# Communication.net
KiCad netlist of a schematic drawn in Altium Designer
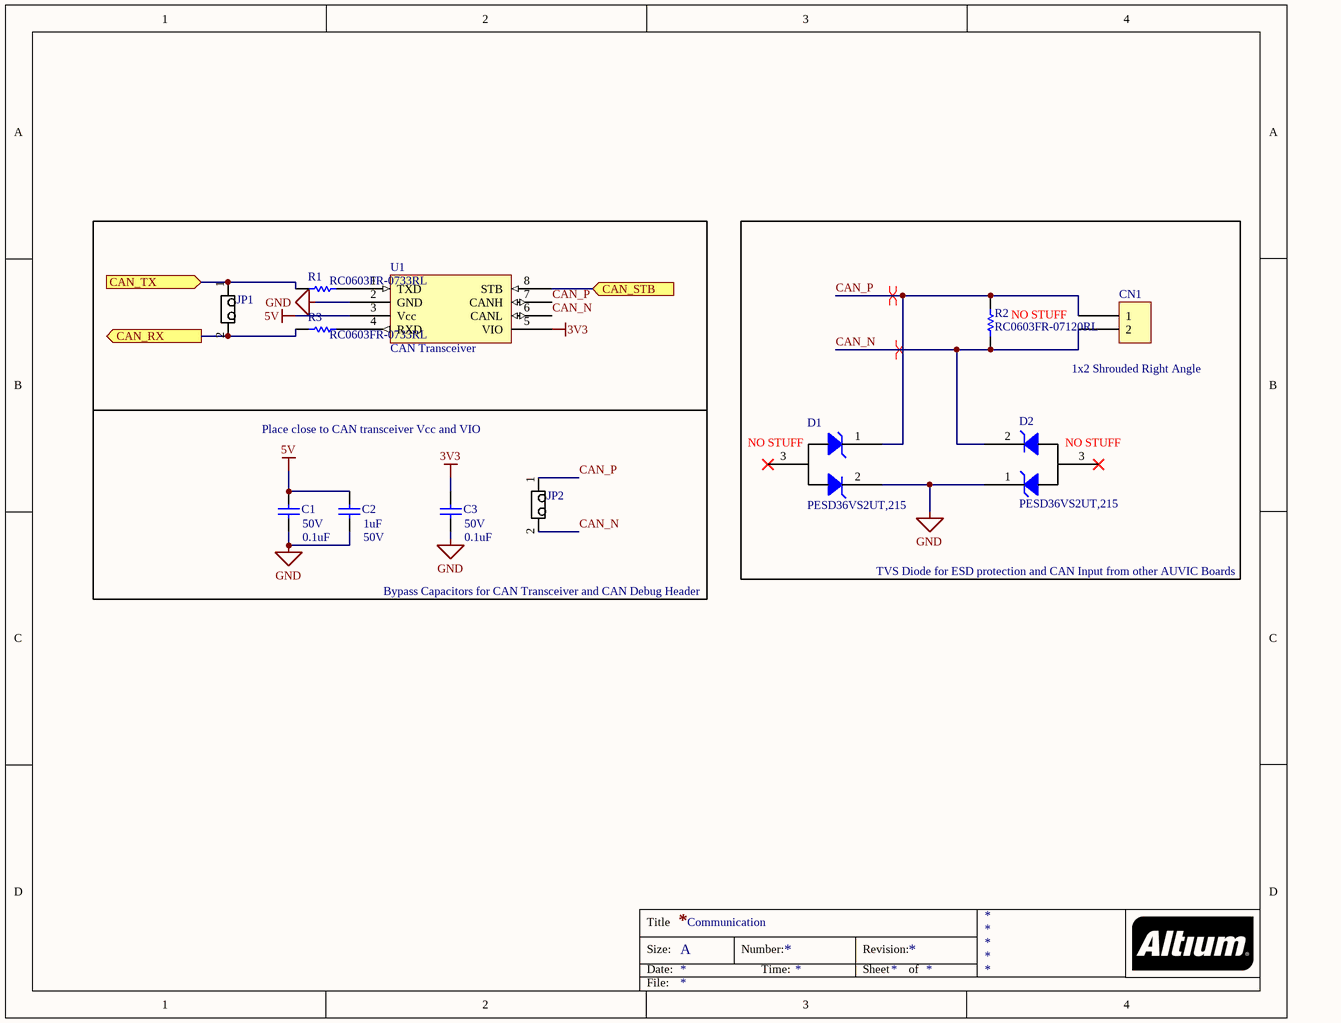
[diagram p0: Communication.SchDoc]

(export (version "E")
  (design (tool "Eeschema 10.0.6"))
  (components
    (comp (ref "C1")
      (value "CL10B104JB8NNNC")
      (footprint "FP-CL10-0_1-IPC_A")
      (description "CAP CER 0.1UF 50V X7R 0603")
      (fields
        (field (name "TOLERANCE") "5%")
        (field (name "VOLTAGE") "50V")
        (field (name "CAPACITANCE") "0.1uF")
      )
      (libsource (lib "AUVIC") (part "CAP-NP-2"))
    )
    (comp (ref "C2")
      (value "CL21B105KBFNNNG")
      (footprint "0803 CAP")
      (description "SAMSUNG ELECTRO-MECHANICS - CL21B105KBFNNNG - MLCC CAPACITORS")
      (fields
        (field (name "TOLERANCE") "10%")
        (field (name "CAPACITANCE") "1uF")
        (field (name "VOLTAGE") "50V")
      )
      (libsource (lib "AUVIC") (part "Symbol"))
    )
    (comp (ref "C3")
      (value "CL10B104JB8NNNC")
      (footprint "FP-CL10-0_1-IPC_A")
      (description "CAP CER 0.1UF 50V X7R 0603")
      (fields
        (field (name "TOLERANCE") "5%")
        (field (name "VOLTAGE") "50V")
        (field (name "CAPACITANCE") "0.1uF")
      )
      (libsource (lib "AUVIC") (part "CAP-NP-2"))
    )
    (comp (ref "CN1")
      (value "1x2 Shrouded Right Angle")
      (footprint "2X1 Female Header")
      (description "02 MTE HDR SRRA LATCH")
      (libsource (lib "AUVIC") (part "1x2 Shrouded Right Angle"))
    )
    (comp (ref "D1")
      (value "PESD36VS2UT,215")
      (footprint "SOT95P245X110-3N")
      (description "TVS DIODE 36V 60V SOT23")
      (fields (field (name "CREATED BY") "Miguel Manguerra"))
      (libsource (lib "AUVIC") (part "PESD36VS2UT,215"))
    )
    (comp (ref "D2")
      (value "PESD36VS2UT,215")
      (footprint "SOT95P245X110-3N")
      (description "TVS DIODE 36V 60V SOT23")
      (fields (field (name "CREATED BY") "Miguel Manguerra"))
      (libsource (lib "AUVIC") (part "PESD36VS2UT,215"))
    )
    (comp (ref "JP1")
      (value "1x2 Male Header")
      (footprint "2X1 Males Header")
      (fields (field (name "MADE BY") "Andy Bates"))
      (libsource (lib "AUVIC") (part "1x2 Male Header"))
    )
    (comp (ref "JP2")
      (value "1x2 Male Header")
      (footprint "2X1 Males Header")
      (fields (field (name "MADE BY") "Andy Bates"))
      (libsource (lib "AUVIC") (part "1x2 Male Header"))
    )
    (comp (ref "R1")
      (value "RC0603FR-0733RL")
      (footprint "RESC1608X55X25LL10T15")
      (description "Res Thick Film 0603 33 Ohm 1% 1/10W +/-100ppm/ßC Molded SMD Paper T/R")
      (fields (field (name "TOLERANCE") "1%"))
      (libsource (lib "AUVIC") (part "RES-2"))
    )
    (comp (ref "R2")
      (value "RC0603FR-07120RL")
      (footprint "RESC1608X55X25ML10T15")
      (description "Res Thick Film 0603 120 Ohm 1% 0.1W(1/10W) ±100ppm/C Epoxy SMD T/R")
      (fields (field (name "TOLERANCE") "1%"))
      (libsource (lib "AUVIC") (part "RES-2"))
    )
    (comp (ref "R3")
      (value "RC0603FR-0733RL")
      (footprint "RESC1608X55X25LL10T15")
      (description "Res Thick Film 0603 33 Ohm 1% 1/10W +/-100ppm/ßC Molded SMD Paper T/R")
      (fields (field (name "TOLERANCE") "1%"))
      (libsource (lib "AUVIC") (part "RES-2"))
    )
    (comp (ref "U1")
      (value "CAN Transceiver")
      (footprint "8-SOIC")
      (description "1/1 Transceiver Half CANbus 8-SO")
      (libsource (lib "AUVIC") (part "CAN Transceiver"))
    )
  )
  (nets
    (net (code "1") (name "/CAN_N") (class "Default")
      (node (ref "CN1") (pin "2") (pinfunction "2_2") (pintype "passive"))
      (node (ref "D2") (pin "2") (pinfunction "Cathode_2_2") (pintype "passive"))
      (node (ref "JP2") (pin "2") (pinfunction "2_2") (pintype "passive"))
      (node (ref "R2") (pin "2") (pinfunction "2_2") (pintype "passive"))
      (node (ref "U1") (pin "6") (pinfunction "CANL_6") (pintype "bidirectional"))
    )
    (net (code "2") (name "/CAN_P") (class "Default")
      (node (ref "CN1") (pin "1") (pinfunction "1_1") (pintype "passive"))
      (node (ref "D1") (pin "1") (pinfunction "Cathode_1_1") (pintype "passive"))
      (node (ref "JP2") (pin "1") (pinfunction "1_1") (pintype "passive"))
      (node (ref "R2") (pin "1") (pinfunction "1_1") (pintype "passive"))
      (node (ref "U1") (pin "7") (pinfunction "CANH_7") (pintype "bidirectional"))
    )
    (net (code "3") (name "/CAN_RX") (class "Default")
      (node (ref "JP1") (pin "2") (pinfunction "2_2") (pintype "passive"))
      (node (ref "R3") (pin "1") (pinfunction "1_1") (pintype "passive"))
    )
    (net (code "4") (name "/CAN_STB") (class "Default")
      (node (ref "U1") (pin "8") (pinfunction "STB_8") (pintype "input"))
    )
    (net (code "5") (name "/CAN_TX") (class "Default")
      (node (ref "JP1") (pin "1") (pinfunction "1_1") (pintype "passive"))
      (node (ref "R1") (pin "1") (pinfunction "1_1") (pintype "passive"))
    )
    (net (code "6") (name "3V3") (class "Default")
      (node (ref "C3") (pin "1") (pinfunction "1_1") (pintype "passive"))
      (node (ref "U1") (pin "5") (pinfunction "VIO_5") (pintype "passive"))
    )
    (net (code "7") (name "5V") (class "Default")
      (node (ref "C1") (pin "1") (pinfunction "1_1") (pintype "passive"))
      (node (ref "C2") (pin "1") (pinfunction "1_1") (pintype "passive"))
      (node (ref "U1") (pin "3") (pinfunction "Vcc_3") (pintype "power_in"))
    )
    (net (code "8") (name "GND") (class "Default")
      (node (ref "C1") (pin "2") (pinfunction "2_2") (pintype "passive"))
      (node (ref "C2") (pin "2") (pinfunction "2_2") (pintype "passive"))
      (node (ref "C3") (pin "2") (pinfunction "2_2") (pintype "passive"))
      (node (ref "D1") (pin "2") (pinfunction "Cathode_2_2") (pintype "passive"))
      (node (ref "D2") (pin "1") (pinfunction "Cathode_1_1") (pintype "passive"))
      (node (ref "U1") (pin "2") (pinfunction "GND_2") (pintype "power_in"))
    )
    (net (code "9") (name "Net-(U1-RXD)") (class "Default")
      (node (ref "R3") (pin "2") (pinfunction "2_2") (pintype "passive"))
      (node (ref "U1") (pin "4") (pinfunction "RXD_4") (pintype "output"))
    )
    (net (code "10") (name "Net-(U1-TXD)") (class "Default")
      (node (ref "R1") (pin "2") (pinfunction "2_2") (pintype "passive"))
      (node (ref "U1") (pin "1") (pinfunction "TXD_1") (pintype "input"))
    )
    (net (code "11") (name "unconnected-(D1-Common_Anode-Pad3)") (class "Default")
      (node (ref "D1") (pin "3") (pinfunction "Common_Anode_3") (pintype "passive"))
    )
    (net (code "12") (name "unconnected-(D2-Common_Anode-Pad3)") (class "Default")
      (node (ref "D2") (pin "3") (pinfunction "Common_Anode_3") (pintype "passive"))
    )
  )
)
